# master-noavr.net
KiCad netlist of a schematic drawn in EAGLE
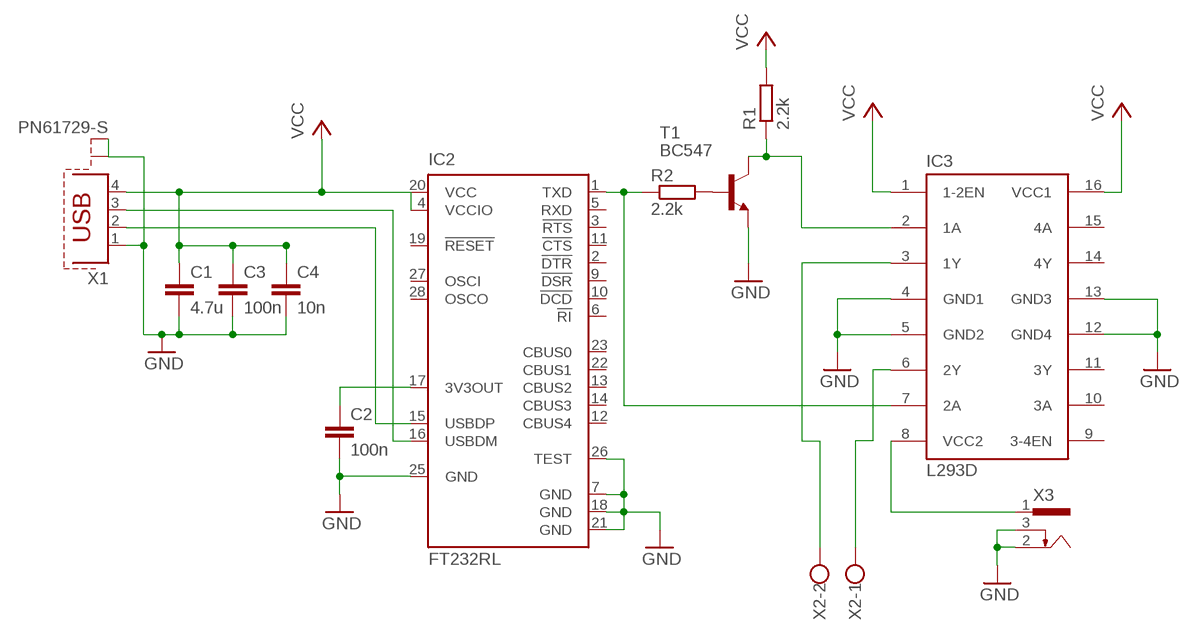
[diagram p0: schematic, sheet 1]

(export (version "E")
  (design (tool "Eeschema 10.0.6"))
  (components
    (comp (ref "C1")
      (value "4.7u")
      (footprint "eagle-import:C025-025X050")
      (libsource (lib "eagle-import") (part "C-EU025-025X050"))
    )
    (comp (ref "C2")
      (value "100n")
      (footprint "eagle-import:C025-025X050")
      (libsource (lib "eagle-import") (part "C-EU025-025X050"))
    )
    (comp (ref "C3")
      (value "100n")
      (footprint "eagle-import:C025-025X050")
      (libsource (lib "eagle-import") (part "C-EU025-025X050"))
    )
    (comp (ref "C4")
      (value "10n")
      (footprint "eagle-import:C025-025X050")
      (libsource (lib "eagle-import") (part "C-EU025-025X050"))
    )
    (comp (ref "IC2")
      (value "FT232RL")
      (footprint "eagle-import:SSOP28")
      (libsource (lib "eagle-import") (part "FT232RL"))
    )
    (comp (ref "IC3")
      (value "L293D")
      (footprint "eagle-import:DIL16")
      (libsource (lib "eagle-import") (part "L293D"))
    )
    (comp (ref "R1")
      (value "2.2k")
      (footprint "eagle-import:0309_10")
      (libsource (lib "eagle-import") (part "R-EU_0309/10"))
    )
    (comp (ref "R2")
      (value "2.2k")
      (footprint "eagle-import:0309_10")
      (libsource (lib "eagle-import") (part "R-EU_0309/10"))
    )
    (comp (ref "T1")
      (value "BC547")
      (footprint "eagle-import:TO92")
      (libsource (lib "eagle-import") (part "BC547"))
    )
    (comp (ref "X1")
      (value "PN61729-S")
      (footprint "eagle-import:PN61729-S")
      (libsource (lib "eagle-import") (part "PN61729-S"))
    )
    (comp (ref "X2")
      (value "W237-102")
      (footprint "eagle-import:W237-102")
      (fields (field (name "MPN") "237-102"))
      (libsource (lib "eagle-import") (part "W237-102"))
    )
    (comp (ref "X3")
      (value "733980-62")
      (footprint "eagle-import:733980-62")
      (libsource (lib "eagle-import") (part "73398?0-62"))
    )
  )
  (nets
    (net (code "1") (name "GND") (class "Default")
      (node (ref "C1") (pin "2") (pinfunction "2_2") (pintype "passive"))
      (node (ref "C2") (pin "2") (pinfunction "2_2") (pintype "passive"))
      (node (ref "C3") (pin "2") (pinfunction "2_2") (pintype "passive"))
      (node (ref "C4") (pin "2") (pinfunction "2_2") (pintype "passive"))
      (node (ref "IC2") (pin "18") (pinfunction "GND_18") (pintype "power_in"))
      (node (ref "IC2") (pin "21") (pinfunction "GND_21") (pintype "power_in"))
      (node (ref "IC2") (pin "25") (pinfunction "GND_25") (pintype "power_in"))
      (node (ref "IC2") (pin "26") (pinfunction "TEST_26") (pintype "input"))
      (node (ref "IC2") (pin "7") (pinfunction "GND_7") (pintype "power_in"))
      (node (ref "IC3") (pin "12") (pinfunction "GND4_12") (pintype "power_in"))
      (node (ref "IC3") (pin "13") (pinfunction "GND3_13") (pintype "power_in"))
      (node (ref "IC3") (pin "4") (pinfunction "GND1_4") (pintype "power_in"))
      (node (ref "IC3") (pin "5") (pinfunction "GND2_5") (pintype "power_in"))
      (node (ref "T1") (pin "1") (pinfunction "E_1") (pintype "passive"))
      (node (ref "X1") (pin "1") (pinfunction "1_1") (pintype "passive"))
      (node (ref "X1") (pin "S1") (pinfunction "S1_S1") (pintype "passive"))
      (node (ref "X1") (pin "S2") (pinfunction "S2_S2") (pintype "passive"))
      (node (ref "X3") (pin "2") (pinfunction "2_2") (pintype "passive"))
      (node (ref "X3") (pin "3") (pinfunction "3_3") (pintype "passive"))
    )
    (net (code "2") (name "Net-(IC2-3V3OUT)") (class "Default")
      (node (ref "C2") (pin "1") (pinfunction "1_1") (pintype "passive"))
      (node (ref "IC2") (pin "17") (pinfunction "3V3OUT_17") (pintype "output"))
    )
    (net (code "3") (name "Net-(IC2-TXD)") (class "Default")
      (node (ref "IC2") (pin "1") (pinfunction "TXD_1") (pintype "output"))
      (node (ref "IC3") (pin "7") (pinfunction "2A_7") (pintype "input"))
      (node (ref "R2") (pin "1") (pinfunction "1_1") (pintype "passive"))
    )
    (net (code "4") (name "Net-(IC2-USBDM)") (class "Default")
      (node (ref "IC2") (pin "16") (pinfunction "USBDM_16") (pintype "bidirectional"))
      (node (ref "X1") (pin "3") (pinfunction "3_3") (pintype "passive"))
    )
    (net (code "5") (name "Net-(IC2-USBDP)") (class "Default")
      (node (ref "IC2") (pin "15") (pinfunction "USBDP_15") (pintype "bidirectional"))
      (node (ref "X1") (pin "2") (pinfunction "2_2") (pintype "passive"))
    )
    (net (code "6") (name "Net-(IC3-1A)") (class "Default")
      (node (ref "IC3") (pin "2") (pinfunction "1A_2") (pintype "input"))
      (node (ref "R1") (pin "1") (pinfunction "1_1") (pintype "passive"))
      (node (ref "T1") (pin "3") (pinfunction "C_3") (pintype "passive"))
    )
    (net (code "7") (name "Net-(IC3-1Y)") (class "Default")
      (node (ref "IC3") (pin "3") (pinfunction "1Y_3") (pintype "output"))
      (node (ref "X2") (pin "2") (pinfunction "KL_2") (pintype "passive"))
    )
    (net (code "8") (name "Net-(IC3-2Y)") (class "Default")
      (node (ref "IC3") (pin "6") (pinfunction "2Y_6") (pintype "output"))
      (node (ref "X2") (pin "1") (pinfunction "KL_1") (pintype "passive"))
    )
    (net (code "9") (name "Net-(IC3-VCC2)") (class "Default")
      (node (ref "IC3") (pin "8") (pinfunction "VCC2_8") (pintype "power_in"))
      (node (ref "X3") (pin "1") (pinfunction "1_1") (pintype "passive"))
    )
    (net (code "10") (name "Net-(T1-B)") (class "Default")
      (node (ref "R2") (pin "2") (pinfunction "2_2") (pintype "passive"))
      (node (ref "T1") (pin "2") (pinfunction "B_2") (pintype "passive"))
    )
    (net (code "11") (name "VCC") (class "Default")
      (node (ref "C1") (pin "1") (pinfunction "1_1") (pintype "passive"))
      (node (ref "C3") (pin "1") (pinfunction "1_1") (pintype "passive"))
      (node (ref "C4") (pin "1") (pinfunction "1_1") (pintype "passive"))
      (node (ref "IC2") (pin "20") (pinfunction "VCC_20") (pintype "power_in"))
      (node (ref "IC2") (pin "4") (pinfunction "VCCIO_4") (pintype "power_in"))
      (node (ref "IC3") (pin "1") (pinfunction "1-2EN_1") (pintype "input"))
      (node (ref "IC3") (pin "16") (pinfunction "VCC1_16") (pintype "power_in"))
      (node (ref "R1") (pin "2") (pinfunction "2_2") (pintype "passive"))
      (node (ref "X1") (pin "4") (pinfunction "4_4") (pintype "passive"))
    )
    (net (code "12") (name "unconnected-(IC2-CBUS0-Pad23)") (class "Default")
      (node (ref "IC2") (pin "23") (pinfunction "CBUS0_23") (pintype "bidirectional"))
    )
    (net (code "13") (name "unconnected-(IC2-CBUS1-Pad22)") (class "Default")
      (node (ref "IC2") (pin "22") (pinfunction "CBUS1_22") (pintype "bidirectional"))
    )
    (net (code "14") (name "unconnected-(IC2-CBUS2-Pad13)") (class "Default")
      (node (ref "IC2") (pin "13") (pinfunction "CBUS2_13") (pintype "bidirectional"))
    )
    (net (code "15") (name "unconnected-(IC2-CBUS3-Pad14)") (class "Default")
      (node (ref "IC2") (pin "14") (pinfunction "CBUS3_14") (pintype "bidirectional"))
    )
    (net (code "16") (name "unconnected-(IC2-CBUS4-Pad12)") (class "Default")
      (node (ref "IC2") (pin "12") (pinfunction "CBUS4_12") (pintype "bidirectional"))
    )
    (net (code "17") (name "unconnected-(IC2-OSCI-Pad27)") (class "Default")
      (node (ref "IC2") (pin "27") (pinfunction "OSCI_27") (pintype "input"))
    )
    (net (code "18") (name "unconnected-(IC2-OSCO-Pad28)") (class "Default")
      (node (ref "IC2") (pin "28") (pinfunction "OSCO_28") (pintype "output"))
    )
    (net (code "19") (name "unconnected-(IC2-RXD-Pad5)") (class "Default")
      (node (ref "IC2") (pin "5") (pinfunction "RXD_5") (pintype "input"))
    )
    (net (code "20") (name "unconnected-(IC2-~{CTS}-Pad11)") (class "Default")
      (node (ref "IC2") (pin "11") (pinfunction "~{CTS}_11") (pintype "input"))
    )
    (net (code "21") (name "unconnected-(IC2-~{DCD}-Pad10)") (class "Default")
      (node (ref "IC2") (pin "10") (pinfunction "~{DCD}_10") (pintype "input"))
    )
    (net (code "22") (name "unconnected-(IC2-~{DSR}-Pad9)") (class "Default")
      (node (ref "IC2") (pin "9") (pinfunction "~{DSR}_9") (pintype "input"))
    )
    (net (code "23") (name "unconnected-(IC2-~{DTR}-Pad2)") (class "Default")
      (node (ref "IC2") (pin "2") (pinfunction "~{DTR}_2") (pintype "output"))
    )
    (net (code "24") (name "unconnected-(IC2-~{RESET}-Pad19)") (class "Default")
      (node (ref "IC2") (pin "19") (pinfunction "~{RESET}_19") (pintype "input"))
    )
    (net (code "25") (name "unconnected-(IC2-~{RI}-Pad6)") (class "Default")
      (node (ref "IC2") (pin "6") (pinfunction "~{RI}_6") (pintype "input"))
    )
    (net (code "26") (name "unconnected-(IC2-~{RTS}-Pad3)") (class "Default")
      (node (ref "IC2") (pin "3") (pinfunction "~{RTS}_3") (pintype "output"))
    )
    (net (code "27") (name "unconnected-(IC3-3-4EN-Pad9)") (class "Default")
      (node (ref "IC3") (pin "9") (pinfunction "3-4EN_9") (pintype "input"))
    )
    (net (code "28") (name "unconnected-(IC3-3A-Pad10)") (class "Default")
      (node (ref "IC3") (pin "10") (pinfunction "3A_10") (pintype "input"))
    )
    (net (code "29") (name "unconnected-(IC3-3Y-Pad11)") (class "Default")
      (node (ref "IC3") (pin "11") (pinfunction "3Y_11") (pintype "output"))
    )
    (net (code "30") (name "unconnected-(IC3-4A-Pad15)") (class "Default")
      (node (ref "IC3") (pin "15") (pinfunction "4A_15") (pintype "input"))
    )
    (net (code "31") (name "unconnected-(IC3-4Y-Pad14)") (class "Default")
      (node (ref "IC3") (pin "14") (pinfunction "4Y_14") (pintype "output"))
    )
  )
)
